# constantCV.net
KiCad netlist of a schematic drawn in Altium Designer
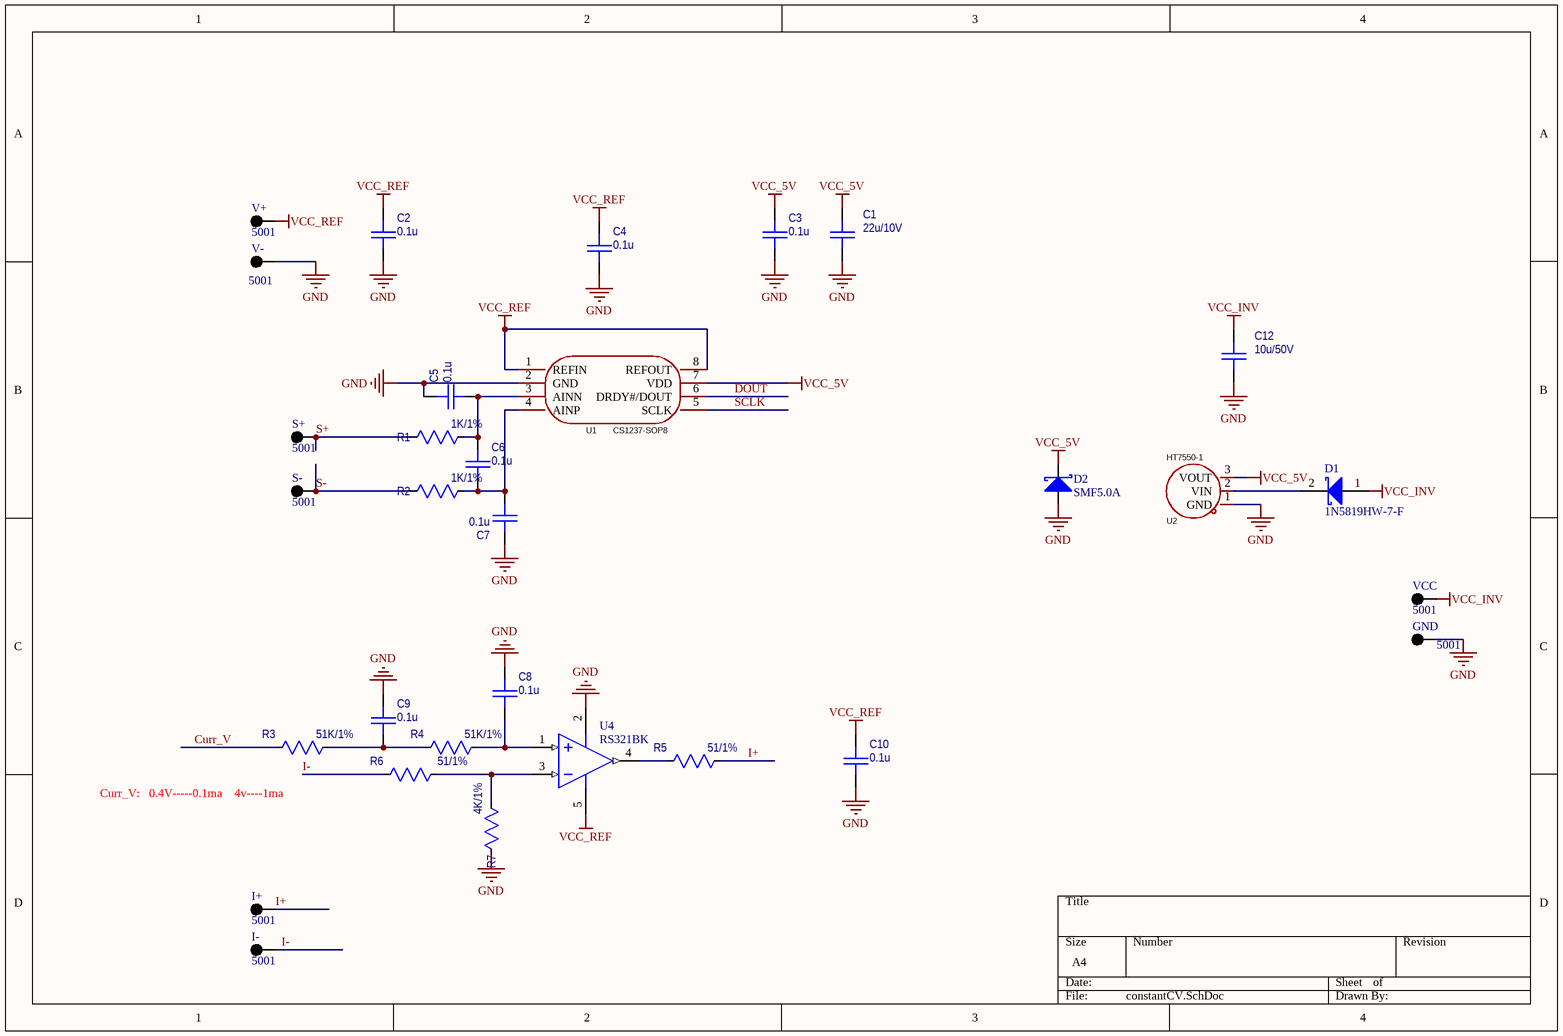
[diagram p0: constantCV.SchDoc]

(export (version "E")
  (design (tool "Eeschema 10.0.6"))
  (components
    (comp (ref "C1")
      (value "22u/10V")
      (footprint "CAPC2012X127N_0805")
      (description "Capacitor, MLCC")
      (fields (field (name "MANUFACTURER") "KEMET") (field (name "PARTNUMBER") "C0805C106K8PACTU"))
      (libsource (lib "Karl") (part "Capacitor_0805"))
    )
    (comp (ref "C2")
      (value "0.1u")
      (footprint "CAPC1608X092N_0603")
      (description "Capacitor, MLCC")
      (fields (field (name "MANUFACTURER") "KEMET") (field (name "PARTNUMBER") "C0603C104M5RACTU"))
      (libsource (lib "Karl") (part "Capacitor_0603"))
    )
    (comp (ref "C3")
      (value "0.1u")
      (footprint "CAPC1608X092N_0603")
      (description "Capacitor, MLCC")
      (fields (field (name "MANUFACTURER") "KEMET") (field (name "PARTNUMBER") "C0603C104M5RACTU"))
      (libsource (lib "Karl") (part "Capacitor_0603"))
    )
    (comp (ref "C4")
      (value "0.1u")
      (footprint "CAPC1608X092N_0603")
      (description "Capacitor, MLCC")
      (fields (field (name "MANUFACTURER") "KEMET") (field (name "PARTNUMBER") "C0603C104M5RACTU"))
      (libsource (lib "Karl") (part "Capacitor_0603"))
    )
    (comp (ref "C5")
      (value "0.1u")
      (footprint "CAPC1608X092N_0603")
      (description "Capacitor, MLCC")
      (fields (field (name "MANUFACTURER") "KEMET") (field (name "PARTNUMBER") "C0603C104M5RACTU"))
      (libsource (lib "Karl") (part "Capacitor_0603"))
    )
    (comp (ref "C6")
      (value "0.1u")
      (footprint "CAPC1608X092N_0603")
      (description "Capacitor, MLCC")
      (fields (field (name "MANUFACTURER") "KEMET") (field (name "PARTNUMBER") "C0603C104M5RACTU"))
      (libsource (lib "Karl") (part "Capacitor_0603"))
    )
    (comp (ref "C7")
      (value "0.1u")
      (footprint "CAPC1608X092N_0603")
      (description "Capacitor, MLCC")
      (fields (field (name "MANUFACTURER") "KEMET") (field (name "PARTNUMBER") "C0603C104M5RACTU"))
      (libsource (lib "Karl") (part "Capacitor_0603"))
    )
    (comp (ref "C8")
      (value "0.1u")
      (footprint "CAPC1608X092N_0603")
      (description "Capacitor, MLCC")
      (fields (field (name "MANUFACTURER") "KEMET") (field (name "PARTNUMBER") "C0603C104M5RACTU"))
      (libsource (lib "Karl") (part "Capacitor_0603"))
    )
    (comp (ref "C9")
      (value "0.1u")
      (footprint "CAPC1608X092N_0603")
      (description "Capacitor, MLCC")
      (fields (field (name "MANUFACTURER") "KEMET") (field (name "PARTNUMBER") "C0603C104M5RACTU"))
      (libsource (lib "Karl") (part "Capacitor_0603"))
    )
    (comp (ref "C10")
      (value "0.1u")
      (footprint "CAPC1608X092N_0603")
      (description "Capacitor, MLCC")
      (fields (field (name "MANUFACTURER") "KEMET") (field (name "PARTNUMBER") "C0603C104M5RACTU"))
      (libsource (lib "Karl") (part "Capacitor_0603"))
    )
    (comp (ref "C12")
      (value "10u/50V")
      (footprint "CAPC2012X127N_0805")
      (description "Capacitor, MLCC")
      (fields (field (name "MANUFACTURER") "KEMET") (field (name "PARTNUMBER") "C0805C106K8PACTU"))
      (libsource (lib "Karl") (part "Capacitor_0805"))
    )
    (comp (ref "D1")
      (value "1N5819HW-7-F")
      (footprint "DIOD-SOD-123-2_V")
      (libsource (lib "Bogen") (part "1N5819HW-7-F"))
    )
    (comp (ref "D2") (value "SMF5.0A") (footprint "SOD123") (libsource (lib "*") (part "DIODE S")))
    (comp (ref "GND")
      (value "5001")
      (footprint "KSTN-5001")
      (description "Test Point, Black, 1-Pin THD, RoHS, Bulk")
      (fields (field (name "MANUFACTURER") "Keystone"))
      (libsource (lib "Bogen") (part "5001"))
    )
    (comp (ref "I+")
      (value "5001")
      (footprint "KSTN-5001")
      (description "Test Point, Black, 1-Pin THD, RoHS, Bulk")
      (fields (field (name "MANUFACTURER") "Keystone"))
      (libsource (lib "Bogen") (part "5001"))
    )
    (comp (ref "I-")
      (value "5001")
      (footprint "KSTN-5001")
      (description "Test Point, Black, 1-Pin THD, RoHS, Bulk")
      (fields (field (name "MANUFACTURER") "Keystone"))
      (libsource (lib "Bogen") (part "5001"))
    )
    (comp (ref "R1")
      (value "1K/1%")
      (footprint "RESC1608X055N_0603")
      (description "Resistor, Standard")
      (fields (field (name "MANUFACTURER") "Yageo") (field (name "PARTNUMBER") "RC0603FR-1075KL"))
      (libsource (lib "Karl") (part "Resistor_0603"))
    )
    (comp (ref "R2")
      (value "1K/1%")
      (footprint "RESC1608X055N_0603")
      (description "Resistor, Standard")
      (fields (field (name "MANUFACTURER") "Yageo") (field (name "PARTNUMBER") "RC0603FR-1075KL"))
      (libsource (lib "Karl") (part "Resistor_0603"))
    )
    (comp (ref "R3")
      (value "51K/1%")
      (footprint "RESC1608X055N_0603")
      (description "Resistor, Standard")
      (fields (field (name "MANUFACTURER") "Yageo") (field (name "PARTNUMBER") "RC0603FR-1075KL"))
      (libsource (lib "Karl") (part "Resistor_0603"))
    )
    (comp (ref "R4")
      (value "51K/1%")
      (footprint "RESC1608X055N_0603")
      (description "Resistor, Standard")
      (fields (field (name "MANUFACTURER") "Yageo") (field (name "PARTNUMBER") "RC0603FR-1075KL"))
      (libsource (lib "Karl") (part "Resistor_0603"))
    )
    (comp (ref "R5")
      (value "51/1%")
      (footprint "RESC1608X055N_0603")
      (description "Resistor, Standard")
      (fields (field (name "MANUFACTURER") "Yageo") (field (name "PARTNUMBER") "RC0603FR-1075KL"))
      (libsource (lib "Karl") (part "Resistor_0603"))
    )
    (comp (ref "R6")
      (value "51/1%")
      (footprint "RESC1608X055N_0603")
      (description "Resistor, Standard")
      (fields (field (name "MANUFACTURER") "Yageo") (field (name "PARTNUMBER") "RC0603FR-1075KL"))
      (libsource (lib "Karl") (part "Resistor_0603"))
    )
    (comp (ref "R7")
      (value "4K/1%")
      (footprint "RESC1608X055N_0603")
      (description "Resistor, Standard")
      (fields (field (name "MANUFACTURER") "Yageo") (field (name "PARTNUMBER") "RC0603FR-1075KL"))
      (libsource (lib "Karl") (part "Resistor_0603"))
    )
    (comp (ref "S+")
      (value "5001")
      (footprint "KSTN-5001")
      (description "Test Point, Black, 1-Pin THD, RoHS, Bulk")
      (fields (field (name "MANUFACTURER") "Keystone"))
      (libsource (lib "Bogen") (part "5001"))
    )
    (comp (ref "S-")
      (value "5001")
      (footprint "KSTN-5001")
      (description "Test Point, Black, 1-Pin THD, RoHS, Bulk")
      (fields (field (name "MANUFACTURER") "Keystone"))
      (libsource (lib "Bogen") (part "5001"))
    )
    (comp (ref "U1")
      (value "CS1237-SOP8")
      (footprint "SOIC-8_L5.0-W4.0-P1.27-LS6.0-BL:SOIC-8_L5.0-W4.0-P1.27-LS6.0-BL")
      (fields (field (name "MANUFACTURER") "CHIPSEA(芯海科技)"))
      (libsource (lib "altium-import") (part "root_0_CS1237-SOP8_"))
    )
    (comp (ref "U2")
      (value "HT7550-1")
      (footprint "SOT-89_L4.5-W2.5-P1.50-LS4.2-BR:SOT-89_L4.5-W2.5-P1.50-LS4.2-BR")
      (fields (field (name "MANUFACTURER") "UMW(友台半导体)"))
      (libsource (lib "altium-import") (part "root_2_HT7550-1_C347189_"))
    )
    (comp (ref "U4")
      (value "RS321BK")
      (footprint "SHBL-SOT-23-5_N")
      (fields
        (field (name "MANUFACTURER") "Shanghai Belling")
        (field (name "PARTNUMBER") "BL321LFR")
        (field (name "PUBLISHER") "Bolgen Studio")
      )
      (libsource (lib "Bogen") (part "BL321LFR"))
    )
    (comp (ref "V+")
      (value "5001")
      (footprint "KSTN-5001")
      (description "Test Point, Black, 1-Pin THD, RoHS, Bulk")
      (fields (field (name "MANUFACTURER") "Keystone"))
      (libsource (lib "Bogen") (part "5001"))
    )
    (comp (ref "V-")
      (value "5001")
      (footprint "KSTN-5001")
      (description "Test Point, Black, 1-Pin THD, RoHS, Bulk")
      (fields (field (name "MANUFACTURER") "Keystone"))
      (libsource (lib "Bogen") (part "5001"))
    )
    (comp (ref "VCC")
      (value "5001")
      (footprint "KSTN-5001")
      (description "Test Point, Black, 1-Pin THD, RoHS, Bulk")
      (fields (field (name "MANUFACTURER") "Keystone"))
      (libsource (lib "Bogen") (part "5001"))
    )
  )
  (nets
    (net (code "1") (name "/Curr_V") (class "Default")
      (node (ref "R3") (pin "2") (pinfunction "2_2") (pintype "passive"))
    )
    (net (code "2") (name "/DOUT") (class "Default")
      (node (ref "U1") (pin "6") (pinfunction "DRDY#/DOUT_6") (pintype "passive"))
    )
    (net (code "3") (name "/I+") (class "Default")
      (node (ref "I+") (pin "1") (pintype "passive"))
      (node (ref "R5") (pin "1") (pinfunction "1_1") (pintype "passive"))
    )
    (net (code "4") (name "/I-") (class "Default")
      (node (ref "I-") (pin "1") (pintype "passive"))
      (node (ref "R6") (pin "2") (pinfunction "2_2") (pintype "passive"))
    )
    (net (code "5") (name "/S+") (class "Default")
      (node (ref "R1") (pin "2") (pinfunction "2_2") (pintype "passive"))
      (node (ref "S+") (pin "1") (pintype "passive"))
    )
    (net (code "6") (name "/S-") (class "Default")
      (node (ref "R2") (pin "2") (pinfunction "2_2") (pintype "passive"))
      (node (ref "S-") (pin "1") (pintype "passive"))
    )
    (net (code "7") (name "/SCLK") (class "Default")
      (node (ref "U1") (pin "5") (pinfunction "SCLK_5") (pintype "passive"))
    )
    (net (code "8") (name "GND") (class "Default")
      (node (ref "C1") (pin "2") (pinfunction "2_2") (pintype "passive"))
      (node (ref "C10") (pin "2") (pinfunction "2_2") (pintype "passive"))
      (node (ref "C12") (pin "2") (pinfunction "2_2") (pintype "passive"))
      (node (ref "C2") (pin "2") (pinfunction "2_2") (pintype "passive"))
      (node (ref "C3") (pin "2") (pinfunction "2_2") (pintype "passive"))
      (node (ref "C4") (pin "2") (pinfunction "2_2") (pintype "passive"))
      (node (ref "C5") (pin "1") (pinfunction "1_1") (pintype "passive"))
      (node (ref "C7") (pin "1") (pinfunction "1_1") (pintype "passive"))
      (node (ref "C8") (pin "1") (pinfunction "1_1") (pintype "passive"))
      (node (ref "C9") (pin "1") (pinfunction "1_1") (pintype "passive"))
      (node (ref "D2") (pin "1") (pinfunction "A_1") (pintype "passive"))
      (node (ref "GND") (pin "1") (pintype "passive"))
      (node (ref "R7") (pin "2") (pinfunction "2_2") (pintype "passive"))
      (node (ref "U1") (pin "2") (pinfunction "GND_2") (pintype "passive"))
      (node (ref "U2") (pin "1") (pinfunction "GND_1") (pintype "passive"))
      (node (ref "U4") (pin "2") (pinfunction "VSS_2") (pintype "power_in"))
      (node (ref "V-") (pin "1") (pintype "passive"))
    )
    (net (code "9") (name "Net-(C9-Pad2)") (class "Default")
      (node (ref "C9") (pin "2") (pinfunction "2_2") (pintype "passive"))
      (node (ref "R3") (pin "1") (pinfunction "1_1") (pintype "passive"))
      (node (ref "R4") (pin "2") (pinfunction "2_2") (pintype "passive"))
    )
    (net (code "10") (name "Net-(D1-K)") (class "Default")
      (node (ref "D1") (pin "2") (pinfunction "K_2") (pintype "passive"))
      (node (ref "U2") (pin "2") (pinfunction "VIN_2") (pintype "passive"))
    )
    (net (code "11") (name "Net-(U1-AINN)") (class "Default")
      (node (ref "C5") (pin "2") (pinfunction "2_2") (pintype "passive"))
      (node (ref "C6") (pin "1") (pinfunction "1_1") (pintype "passive"))
      (node (ref "R1") (pin "1") (pinfunction "1_1") (pintype "passive"))
      (node (ref "U1") (pin "3") (pinfunction "AINN_3") (pintype "passive"))
    )
    (net (code "12") (name "Net-(U1-AINP)") (class "Default")
      (node (ref "C6") (pin "2") (pinfunction "2_2") (pintype "passive"))
      (node (ref "C7") (pin "2") (pinfunction "2_2") (pintype "passive"))
      (node (ref "R2") (pin "1") (pinfunction "1_1") (pintype "passive"))
      (node (ref "U1") (pin "4") (pinfunction "AINP_4") (pintype "passive"))
    )
    (net (code "13") (name "Net-(U4-IN+)") (class "Default")
      (node (ref "C8") (pin "2") (pinfunction "2_2") (pintype "passive"))
      (node (ref "R4") (pin "1") (pinfunction "1_1") (pintype "passive"))
      (node (ref "U4") (pin "1") (pinfunction "IN+_1") (pintype "input"))
    )
    (net (code "14") (name "Net-(U4-IN-)") (class "Default")
      (node (ref "R6") (pin "1") (pinfunction "1_1") (pintype "passive"))
      (node (ref "R7") (pin "1") (pinfunction "1_1") (pintype "passive"))
      (node (ref "U4") (pin "3") (pinfunction "IN-_3") (pintype "input"))
    )
    (net (code "15") (name "Net-(U4-OUT)") (class "Default")
      (node (ref "R5") (pin "2") (pinfunction "2_2") (pintype "passive"))
      (node (ref "U4") (pin "4") (pinfunction "OUT_4") (pintype "output"))
    )
    (net (code "16") (name "VCC_5V") (class "Default")
      (node (ref "C1") (pin "1") (pinfunction "1_1") (pintype "passive"))
      (node (ref "C3") (pin "1") (pinfunction "1_1") (pintype "passive"))
      (node (ref "D2") (pin "2") (pinfunction "K_2") (pintype "passive"))
      (node (ref "U1") (pin "7") (pinfunction "VDD_7") (pintype "passive"))
      (node (ref "U2") (pin "3") (pinfunction "VOUT_3") (pintype "passive"))
    )
    (net (code "17") (name "VCC_INV") (class "Default")
      (node (ref "C12") (pin "1") (pinfunction "1_1") (pintype "passive"))
      (node (ref "D1") (pin "1") (pinfunction "A_1") (pintype "passive"))
      (node (ref "VCC") (pin "1") (pintype "passive"))
    )
    (net (code "18") (name "VCC_REF") (class "Default")
      (node (ref "C10") (pin "1") (pinfunction "1_1") (pintype "passive"))
      (node (ref "C2") (pin "1") (pinfunction "1_1") (pintype "passive"))
      (node (ref "C4") (pin "1") (pinfunction "1_1") (pintype "passive"))
      (node (ref "U1") (pin "1") (pinfunction "REFIN_1") (pintype "passive"))
      (node (ref "U1") (pin "8") (pinfunction "REFOUT_8") (pintype "passive"))
      (node (ref "U4") (pin "5") (pinfunction "VDD_5") (pintype "power_in"))
      (node (ref "V+") (pin "1") (pintype "passive"))
    )
  )
)
